# sensors_f.net
KiCad netlist of a schematic drawn in EAGLE
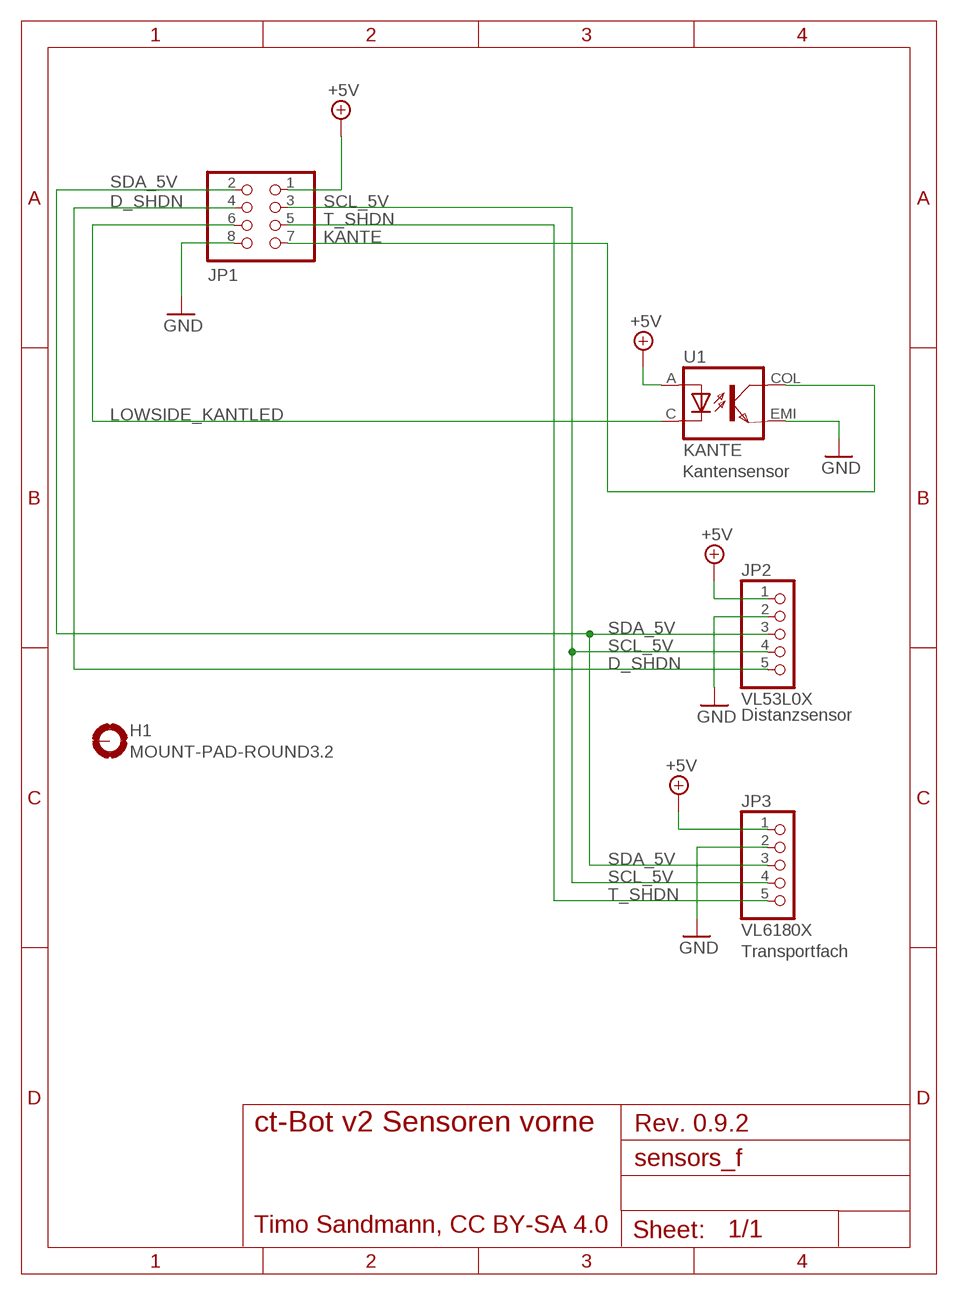
[diagram p0: schematic, sheet 1]

(export (version "E")
  (design (tool "Eeschema 10.0.6"))
  (components
    (comp (ref "H1")
      (value "MOUNT-PAD-ROUND3.2")
      (footprint "eagle-import:3,2-PAD")
      (libsource (lib "eagle-import") (part "MOUNT-PAD-ROUND3.2"))
    )
    (comp (ref "JP1")
      (value "PINHD-2X4")
      (footprint "eagle-import:2X04")
      (libsource (lib "eagle-import") (part "PINHD-2X4"))
    )
    (comp (ref "JP2")
      (value "VL53L0X")
      (footprint "eagle-import:1X05")
      (libsource (lib "eagle-import") (part "PINHD-1X5"))
    )
    (comp (ref "JP3")
      (value "VL6180X")
      (footprint "eagle-import:1X05")
      (libsource (lib "eagle-import") (part "PINHD-1X5"))
    )
    (comp (ref "U1")
      (value "KANTE")
      (footprint "eagle-import:EDGE")
      (libsource (lib "eagle-import") (part "CNY70"))
    )
  )
  (nets
    (net (code "1") (name "+5V") (class "Default")
      (node (ref "JP1") (pin "1") (pinfunction "1_1") (pintype "passive"))
      (node (ref "JP2") (pin "1") (pinfunction "1_1") (pintype "passive"))
      (node (ref "JP3") (pin "1") (pinfunction "1_1") (pintype "passive"))
      (node (ref "U1") (pin "A") (pinfunction "A_A") (pintype "passive"))
    )
    (net (code "2") (name "/D_SHDN") (class "Default")
      (node (ref "JP1") (pin "4") (pinfunction "4_4") (pintype "passive"))
      (node (ref "JP2") (pin "5") (pinfunction "5_5") (pintype "passive"))
    )
    (net (code "3") (name "/KANTE") (class "Default")
      (node (ref "JP1") (pin "7") (pinfunction "7_7") (pintype "passive"))
      (node (ref "U1") (pin "COL") (pinfunction "COL_COL") (pintype "passive"))
    )
    (net (code "4") (name "/LOWSIDE_KANTLED") (class "Default")
      (node (ref "JP1") (pin "6") (pinfunction "6_6") (pintype "passive"))
      (node (ref "U1") (pin "C") (pinfunction "C_C") (pintype "passive"))
    )
    (net (code "5") (name "/SCL_5V") (class "Default")
      (node (ref "JP1") (pin "3") (pinfunction "3_3") (pintype "passive"))
      (node (ref "JP2") (pin "4") (pinfunction "4_4") (pintype "passive"))
      (node (ref "JP3") (pin "4") (pinfunction "4_4") (pintype "passive"))
    )
    (net (code "6") (name "/SDA_5V") (class "Default")
      (node (ref "JP1") (pin "2") (pinfunction "2_2") (pintype "passive"))
      (node (ref "JP2") (pin "3") (pinfunction "3_3") (pintype "passive"))
      (node (ref "JP3") (pin "3") (pinfunction "3_3") (pintype "passive"))
    )
    (net (code "7") (name "/T_SHDN") (class "Default")
      (node (ref "JP1") (pin "5") (pinfunction "5_5") (pintype "passive"))
      (node (ref "JP3") (pin "5") (pinfunction "5_5") (pintype "passive"))
    )
    (net (code "8") (name "GND") (class "Default")
      (node (ref "JP1") (pin "8") (pinfunction "8_8") (pintype "passive"))
      (node (ref "JP2") (pin "2") (pinfunction "2_2") (pintype "passive"))
      (node (ref "JP3") (pin "2") (pinfunction "2_2") (pintype "passive"))
      (node (ref "U1") (pin "EMI") (pinfunction "EMI_EMI") (pintype "passive"))
    )
    (net (code "9") (name "unconnected-(H1-MOUNT-PadB3,2)") (class "Default")
      (node (ref "H1") (pin "B3,2") (pinfunction "MOUNT_B3,2") (pintype "passive"))
    )
  )
)
